# main.net
KiCad netlist of a schematic drawn in EAGLE
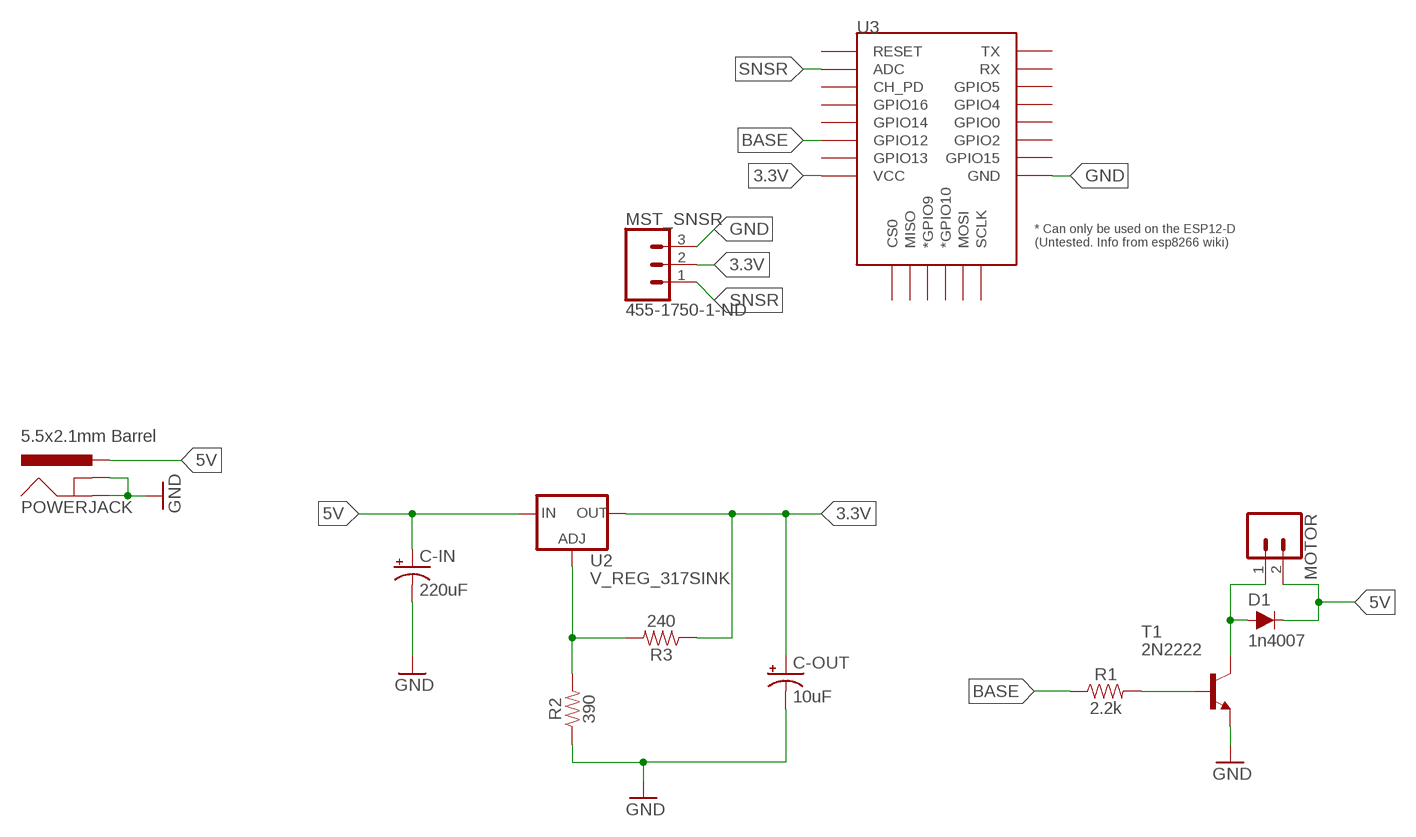
[diagram p0: schematic, sheet 1]

(export (version "E")
  (design (tool "Eeschema 10.0.6"))
  (components
    (comp (ref "C-IN")
      (value "220uF")
      (footprint "eagle-import:CPOL-RADIAL-2.5MM-5MM")
      (libsource (lib "eagle-import") (part "10UF-POLAR-RADIAL-2.5MM-25V-20%"))
    )
    (comp (ref "C-OUT")
      (value "10uF")
      (footprint "eagle-import:CPOL-RADIAL-2.5MM-5MM")
      (libsource (lib "eagle-import") (part "10UF-POLAR-RADIAL-2.5MM-25V-20%"))
    )
    (comp (ref "D1")
      (value "1n4007")
      (footprint "eagle-import:DIODE-1N4148")
      (libsource (lib "eagle-import") (part "DIODE-1N4148"))
    )
    (comp (ref "MOTOR")
      (value "CONN_02")
      (footprint "eagle-import:1X02")
      (libsource (lib "eagle-import") (part "CONN_02"))
    )
    (comp (ref "MST_SNSR")
      (value "455-1750-1-ND")
      (footprint "eagle-import:1X03")
      (libsource (lib "eagle-import") (part "CONN_03"))
    )
    (comp (ref "POWERJACK")
      (value "5.5x2.1mm Barrel")
      (footprint "eagle-import:POWER_JACK_SMD")
      (libsource (lib "eagle-import") (part "POWER_JACKSMD"))
    )
    (comp (ref "R1")
      (value "2.2k")
      (footprint "eagle-import:0805")
      (libsource (lib "eagle-import") (part "0.3OHM-0805-1/8W-1%"))
    )
    (comp (ref "R2")
      (value "390")
      (footprint "eagle-import:0805")
      (libsource (lib "eagle-import") (part "0.3OHM-0805-1/8W-1%"))
    )
    (comp (ref "R3")
      (value "240")
      (footprint "eagle-import:0805")
      (libsource (lib "eagle-import") (part "0.3OHM-0805-1/8W-1%"))
    )
    (comp (ref "T1")
      (value "2N2222")
      (footprint "eagle-import:TO92-EBC-OVAL")
      (libsource (lib "eagle-import") (part "2N2222"))
    )
    (comp (ref "U2")
      (value "V_REG_317SINK")
      (footprint "eagle-import:TO220-ADJ")
      (libsource (lib "eagle-import") (part "V_REG_317SINK"))
    )
    (comp (ref "U3")
      (value "ESP12ESMD")
      (footprint "eagle-import:ESP12E-SMD")
      (libsource (lib "eagle-import") (part "ESP12ESMD"))
    )
  )
  (nets
    (net (code "1") (name "3.3V") (class "Default")
      (node (ref "C-OUT") (pin "1") (pinfunction "+_1") (pintype "passive"))
      (node (ref "MST_SNSR") (pin "2") (pinfunction "2_2") (pintype "passive"))
      (node (ref "R3") (pin "1") (pinfunction "1_1") (pintype "passive"))
      (node (ref "U2") (pin "OUT") (pinfunction "OUT_OUT") (pintype "output"))
      (node (ref "U3") (pin "VCC") (pinfunction "VCC_VCC") (pintype "bidirectional"))
    )
    (net (code "2") (name "5V") (class "Default")
      (node (ref "C-IN") (pin "1") (pinfunction "+_1") (pintype "passive"))
      (node (ref "D1") (pin "C") (pinfunction "C_C") (pintype "passive"))
      (node (ref "MOTOR") (pin "2") (pinfunction "2_2") (pintype "passive"))
      (node (ref "POWERJACK") (pin "VIN0") (pinfunction "PWR_VIN0") (pintype "bidirectional"))
      (node (ref "U2") (pin "IN") (pinfunction "IN_IN") (pintype "input"))
    )
    (net (code "3") (name "BASE") (class "Default")
      (node (ref "R1") (pin "1") (pinfunction "1_1") (pintype "passive"))
      (node (ref "U3") (pin "GPIO12") (pinfunction "GPIO12_GPIO12") (pintype "bidirectional"))
    )
    (net (code "4") (name "GND") (class "Default")
      (node (ref "C-IN") (pin "2") (pinfunction "-_2") (pintype "passive"))
      (node (ref "C-OUT") (pin "2") (pinfunction "-_2") (pintype "passive"))
      (node (ref "MST_SNSR") (pin "3") (pinfunction "3_3") (pintype "passive"))
      (node (ref "POWERJACK") (pin "GND") (pinfunction "GNDBREAK_GND") (pintype "bidirectional"))
      (node (ref "POWERJACK") (pin "P$4") (pinfunction "GND_P$4") (pintype "bidirectional"))
      (node (ref "R2") (pin "1") (pinfunction "1_1") (pintype "passive"))
      (node (ref "T1") (pin "E") (pinfunction "E_E") (pintype "passive"))
      (node (ref "U3") (pin "GND") (pinfunction "GND_GND") (pintype "bidirectional"))
    )
    (net (code "5") (name "Net-(D1-PadA)") (class "Default")
      (node (ref "D1") (pin "A") (pinfunction "A_A") (pintype "passive"))
      (node (ref "MOTOR") (pin "1") (pinfunction "1_1") (pintype "passive"))
      (node (ref "T1") (pin "C") (pinfunction "C_C") (pintype "passive"))
    )
    (net (code "6") (name "Net-(R1-Pad2)") (class "Default")
      (node (ref "R1") (pin "2") (pinfunction "2_2") (pintype "passive"))
      (node (ref "T1") (pin "B") (pinfunction "B_B") (pintype "passive"))
    )
    (net (code "7") (name "Net-(R2-Pad2)") (class "Default")
      (node (ref "R2") (pin "2") (pinfunction "2_2") (pintype "passive"))
      (node (ref "R3") (pin "2") (pinfunction "2_2") (pintype "passive"))
      (node (ref "U2") (pin "ADJ") (pinfunction "ADJ_ADJ") (pintype "input"))
    )
    (net (code "8") (name "SNSR") (class "Default")
      (node (ref "MST_SNSR") (pin "1") (pinfunction "1_1") (pintype "passive"))
      (node (ref "U3") (pin "ADC") (pinfunction "ADC_ADC") (pintype "bidirectional"))
    )
    (net (code "9") (name "unconnected-(U3-*GPIO9-PadGPIO9)") (class "Default")
      (node (ref "U3") (pin "GPIO9") (pinfunction "*GPIO9_GPIO9") (pintype "bidirectional"))
    )
    (net (code "10") (name "unconnected-(U3-*GPIO10-PadGPIO10)") (class "Default")
      (node (ref "U3") (pin "GPIO10") (pinfunction "*GPIO10_GPIO10") (pintype "bidirectional"))
    )
    (net (code "11") (name "unconnected-(U3-PadCH_PD)") (class "Default")
      (node (ref "U3") (pin "CH_PD") (pinfunction "CH_PD_CH_PD") (pintype "bidirectional"))
    )
    (net (code "12") (name "unconnected-(U3-PadCS0)") (class "Default")
      (node (ref "U3") (pin "CS0") (pinfunction "CS0_CS0") (pintype "bidirectional"))
    )
    (net (code "13") (name "unconnected-(U3-PadGPIO0)") (class "Default")
      (node (ref "U3") (pin "GPIO0") (pinfunction "GPIO0_GPIO0") (pintype "bidirectional"))
    )
    (net (code "14") (name "unconnected-(U3-PadGPIO2)") (class "Default")
      (node (ref "U3") (pin "GPIO2") (pinfunction "GPIO2_GPIO2") (pintype "bidirectional"))
    )
    (net (code "15") (name "unconnected-(U3-PadGPIO4)") (class "Default")
      (node (ref "U3") (pin "GPIO4") (pinfunction "GPIO4_GPIO4") (pintype "bidirectional"))
    )
    (net (code "16") (name "unconnected-(U3-PadGPIO5)") (class "Default")
      (node (ref "U3") (pin "GPIO5") (pinfunction "GPIO5_GPIO5") (pintype "bidirectional"))
    )
    (net (code "17") (name "unconnected-(U3-PadGPIO13)") (class "Default")
      (node (ref "U3") (pin "GPIO13") (pinfunction "GPIO13_GPIO13") (pintype "bidirectional"))
    )
    (net (code "18") (name "unconnected-(U3-PadGPIO14)") (class "Default")
      (node (ref "U3") (pin "GPIO14") (pinfunction "GPIO14_GPIO14") (pintype "bidirectional"))
    )
    (net (code "19") (name "unconnected-(U3-PadGPIO15)") (class "Default")
      (node (ref "U3") (pin "GPIO15") (pinfunction "GPIO15_GPIO15") (pintype "bidirectional"))
    )
    (net (code "20") (name "unconnected-(U3-PadGPIO16)") (class "Default")
      (node (ref "U3") (pin "GPIO16") (pinfunction "GPIO16_GPIO16") (pintype "bidirectional"))
    )
    (net (code "21") (name "unconnected-(U3-PadMISO)") (class "Default")
      (node (ref "U3") (pin "MISO") (pinfunction "MISO_MISO") (pintype "bidirectional"))
    )
    (net (code "22") (name "unconnected-(U3-PadMOSI)") (class "Default")
      (node (ref "U3") (pin "MOSI") (pinfunction "MOSI_MOSI") (pintype "bidirectional"))
    )
    (net (code "23") (name "unconnected-(U3-PadRESET)") (class "Default")
      (node (ref "U3") (pin "RESET") (pinfunction "RESET_RESET") (pintype "bidirectional"))
    )
    (net (code "24") (name "unconnected-(U3-PadSCLK)") (class "Default")
      (node (ref "U3") (pin "SCLK") (pinfunction "SCLK_SCLK") (pintype "bidirectional"))
    )
    (net (code "25") (name "unconnected-(U3-RX-PadRXD0)") (class "Default")
      (node (ref "U3") (pin "RXD0") (pinfunction "RX_RXD0") (pintype "bidirectional"))
    )
    (net (code "26") (name "unconnected-(U3-TX-PadTXD0)") (class "Default")
      (node (ref "U3") (pin "TXD0") (pinfunction "TX_TXD0") (pintype "bidirectional"))
    )
  )
)
